# management-i2c.net
KiCad netlist of a schematic drawn in Altium Designer
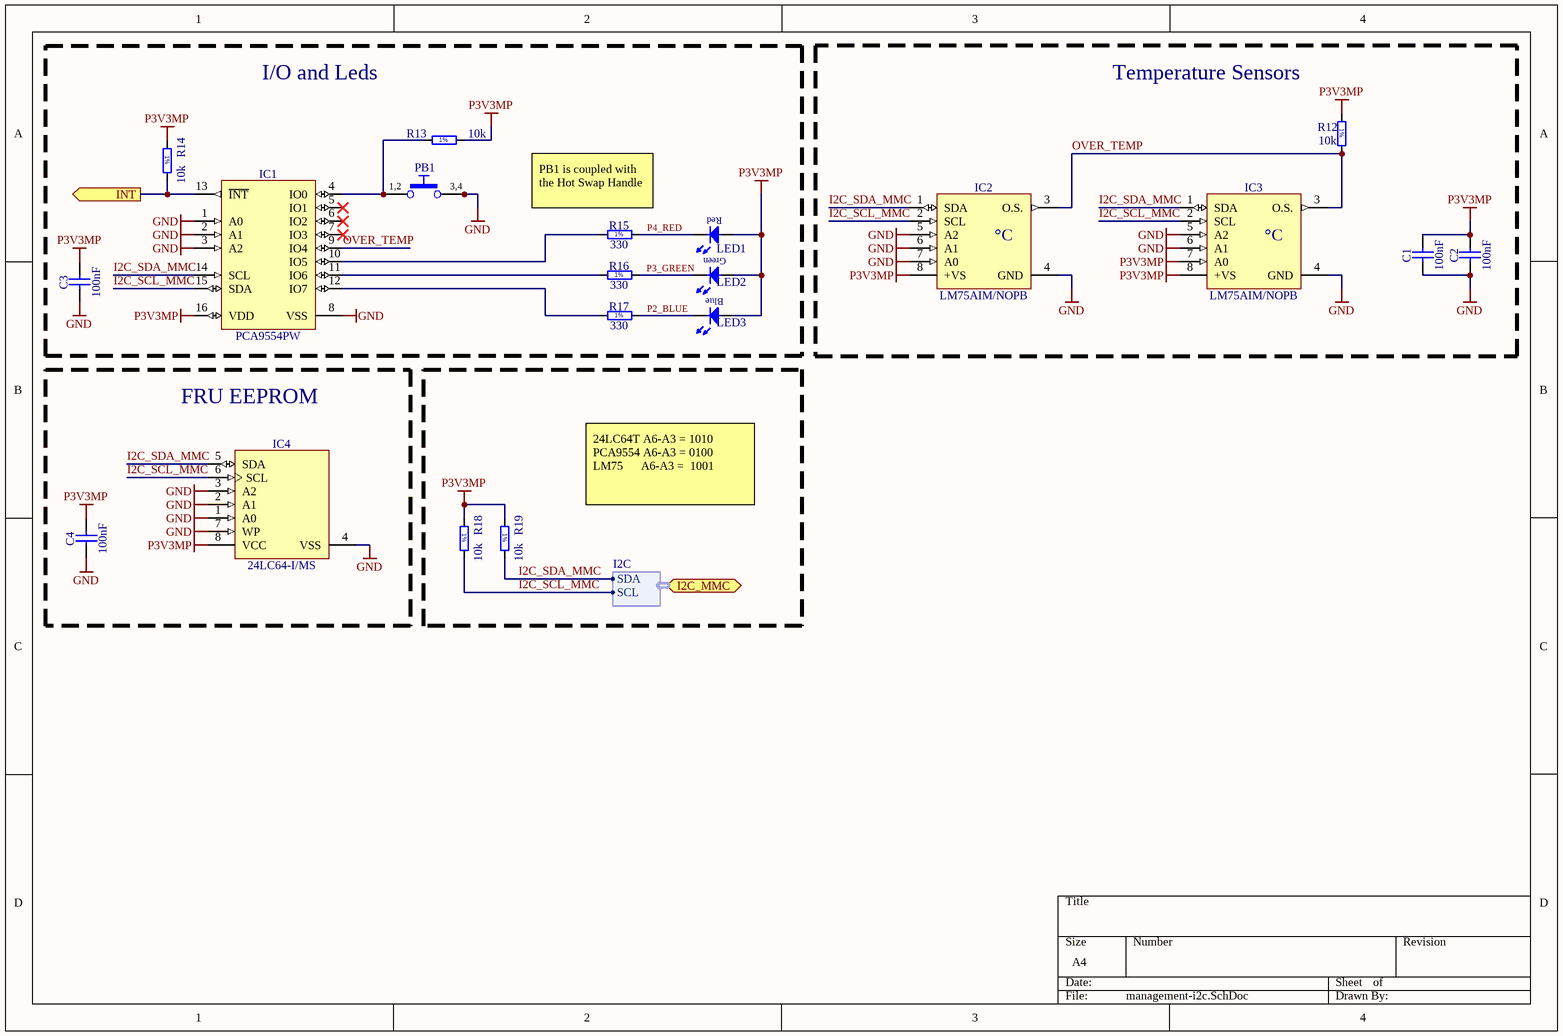
[diagram p0: management-i2c.SchDoc]

(export (version "E")
  (design (tool "Eeschema 10.0.6"))
  (components
    (comp (ref "C1")
      (value "100nF")
      (footprint "CAPC1005X55N")
      (description "Non-polarised capacitor")
      (fields
        (field (name "PART NUMBER") "CC0402_100NF_16V_10%_X7R")
        (field (name "VOLTAGE") "16V")
        (field (name "AUTHOR") "CERN DEM JLC")
      )
      (libsource (lib "Capacitors") (part "Capacitor - non polarized"))
    )
    (comp (ref "C2")
      (value "100nF")
      (footprint "CAPC1005X55N")
      (description "Non-polarised capacitor")
      (fields
        (field (name "PART NUMBER") "CC0402_100NF_16V_10%_X7R")
        (field (name "VOLTAGE") "16V")
        (field (name "AUTHOR") "CERN DEM JLC")
      )
      (libsource (lib "Capacitors") (part "Capacitor - non polarized"))
    )
    (comp (ref "C3")
      (value "100nF")
      (footprint "CAPC1005X55N")
      (description "Non-polarised capacitor")
      (fields
        (field (name "PART NUMBER") "CC0402_100NF_16V_10%_X7R")
        (field (name "VOLTAGE") "16V")
        (field (name "AUTHOR") "CERN DEM JLC")
      )
      (libsource (lib "Capacitors") (part "Capacitor - non polarized"))
    )
    (comp (ref "C4")
      (value "100nF")
      (footprint "CAPC1005X55N")
      (description "Non-polarised capacitor")
      (fields
        (field (name "PART NUMBER") "CC0402_100NF_16V_10%_X7R")
        (field (name "VOLTAGE") "16V")
        (field (name "AUTHOR") "CERN DEM JLC")
      )
      (libsource (lib "Capacitors") (part "Capacitor - non polarized"))
    )
    (comp (ref "IC1")
      (value "PCA9554PW")
      (footprint "SOP65P640X110-16N")
      (description "8-Bit I2C-Bus and SMBus I/O Port with Interrupt")
      (fields (field (name "MANUFACTURER") "NXP SEMICONDUCTORS") (field (name "AUTHOR") "CERN DEM JLC"))
      (libsource (lib "ICs And Semiconductors") (part "PCA9554PW"))
    )
    (comp (ref "IC2")
      (value "LM75AIM/NOPB")
      (footprint "SOIC127P600X175-8N")
      (description "Digital Temperature Sensor and Thermal Watchdog with Two-Wire Interface")
      (fields (field (name "MANUFACTURER") "TEXAS INSTRUMENTS") (field (name "AUTHOR") "CERN DEM JLC"))
      (libsource (lib "ICs And Semiconductors") (part "LM75"))
    )
    (comp (ref "IC3")
      (value "LM75AIM/NOPB")
      (footprint "SOIC127P600X175-8N")
      (description "Digital Temperature Sensor and Thermal Watchdog with Two-Wire Interface")
      (fields (field (name "MANUFACTURER") "TEXAS INSTRUMENTS") (field (name "AUTHOR") "CERN DEM JLC"))
      (libsource (lib "ICs And Semiconductors") (part "LM75"))
    )
    (comp (ref "IC4")
      (value "24LC64-I/MS")
      (footprint "SOP65P490X110-8N")
      (description "64K I2C Serial EEPROM")
      (fields (field (name "MANUFACTURER") "MICROCHIP TECHNOLOGY") (field (name "AUTHOR") "CERN DEM JLC"))
      (libsource (lib "ICs And Semiconductors") (part "24LC64-I/MS"))
    )
    (comp (ref "LED1")
      (value "Red")
      (footprint "LEDC1608X80N_RED")
      (description "LED Red 1C 2A")
      (fields
        (field (name "PART NUMBER") "LED_ROHM_SML-311UTT86K")
        (field (name "MANUFACTURER") "ROHM")
        (field (name "AUTHOR") "CERN DEM JLC")
      )
      (libsource (lib "ICs And Semiconductors") (part "LED Red 1C 2A"))
    )
    (comp (ref "LED2")
      (value "Green")
      (footprint "LED_AVAGO_HSME-C120")
      (description "LED Green 1C 2A")
      (fields
        (field (name "PART NUMBER") "LED_AVAGO_HSME-C120")
        (field (name "MANUFACTURER") "AVAGO TECHNOLOGIES")
        (field (name "AUTHOR") "CERN DEM JMW")
      )
      (libsource (lib "ICs And Semiconductors") (part "LED Green 1C 2A"))
    )
    (comp (ref "LED3")
      (value "Blue")
      (footprint "LED_AVAGO_HSMR-C120")
      (description "LED Blue 1C 2A")
      (fields
        (field (name "PART NUMBER") "LED_AVAGO_HSMR-C120")
        (field (name "MANUFACTURER") "AVAGO TECHNOLOGIES")
        (field (name "AUTHOR") "CERN DEM JLC")
      )
      (libsource (lib "ICs And Semiconductors") (part "LED Blue 1C 2A"))
    )
    (comp (ref "PB1")
      (value "Push Button")
      (footprint "SW_C&K_HDT0001")
      (description "Push-Button Switch SPDT")
      (fields
        (field (name "PART NUMBER") "SW_C&K_HDT0001")
        (field (name "MANUFACTURER") "C&K")
        (field (name "AUTHOR") "CERN DEM JLC")
      )
      (libsource (lib "Eletro-mechanical") (part "PB SPST 12NO-34NO"))
    )
    (comp (ref "R12")
      (value "10k")
      (footprint "RESC1005X40N")
      (description "Resistor - 1%")
      (fields
        (field (name "PART NUMBER") "R0402_10K_1%_0.0625W_100PPM")
        (field (name "POWER") "0.0625W")
        (field (name "AUTHOR") "CERN DEM JLC")
      )
      (libsource (lib "Resistors") (part "Resistor - 1%"))
    )
    (comp (ref "R13")
      (value "10k")
      (footprint "RESC1005X40N")
      (description "Resistor - 1%")
      (fields
        (field (name "PART NUMBER") "R0402_10K_1%_0.0625W_100PPM")
        (field (name "POWER") "0.0625W")
        (field (name "AUTHOR") "CERN DEM JLC")
      )
      (libsource (lib "Resistors") (part "Resistor - 1%"))
    )
    (comp (ref "R14")
      (value "10k")
      (footprint "RESC1005X40N")
      (description "Resistor - 1%")
      (fields
        (field (name "PART NUMBER") "R0402_10K_1%_0.0625W_100PPM")
        (field (name "POWER") "0.0625W")
        (field (name "AUTHOR") "CERN DEM JLC")
      )
      (libsource (lib "Resistors") (part "Resistor - 1%"))
    )
    (comp (ref "R15")
      (value "330")
      (footprint "RESC1608X55N")
      (description "Resistor - 1%")
      (fields
        (field (name "PART NUMBER") "R0603_330R_1%_0.1W_100PPM")
        (field (name "POWER") "0.1W")
        (field (name "AUTHOR") "CERN DEM JLC")
      )
      (libsource (lib "Resistors") (part "Resistor - 1%"))
    )
    (comp (ref "R16")
      (value "330")
      (footprint "RESC1608X55N")
      (description "Resistor - 1%")
      (fields
        (field (name "PART NUMBER") "R0603_330R_1%_0.1W_100PPM")
        (field (name "POWER") "0.1W")
        (field (name "AUTHOR") "CERN DEM JLC")
      )
      (libsource (lib "Resistors") (part "Resistor - 1%"))
    )
    (comp (ref "R17")
      (value "330")
      (footprint "RESC1608X55N")
      (description "Resistor - 1%")
      (fields
        (field (name "PART NUMBER") "R0603_330R_1%_0.1W_100PPM")
        (field (name "POWER") "0.1W")
        (field (name "AUTHOR") "CERN DEM JLC")
      )
      (libsource (lib "Resistors") (part "Resistor - 1%"))
    )
    (comp (ref "R18")
      (value "10k")
      (footprint "RESC1005X40N")
      (description "Resistor - 1%")
      (fields
        (field (name "PART NUMBER") "R0402_10K_1%_0.0625W_100PPM")
        (field (name "POWER") "0.0625W")
        (field (name "AUTHOR") "CERN DEM JLC")
      )
      (libsource (lib "Resistors") (part "Resistor - 1%"))
    )
    (comp (ref "R19")
      (value "10k")
      (footprint "RESC1005X40N")
      (description "Resistor - 1%")
      (fields
        (field (name "PART NUMBER") "R0402_10K_1%_0.0625W_100PPM")
        (field (name "POWER") "0.0625W")
        (field (name "AUTHOR") "CERN DEM JLC")
      )
      (libsource (lib "Resistors") (part "Resistor - 1%"))
    )
  )
  (nets
    (net (code "2") (name "/I2C_SCL_MMC") (class "Default")
      (node (ref "IC1") (pin "15") (pinfunction "SDA_15") (pintype "bidirectional"))
      (node (ref "IC2") (pin "2") (pinfunction "SCL_2") (pintype "input"))
      (node (ref "IC3") (pin "2") (pinfunction "SCL_2") (pintype "input"))
      (node (ref "IC4") (pin "6") (pinfunction "SCL_6") (pintype "input"))
      (node (ref "R18") (pin "2") (pinfunction "2_2") (pintype "passive"))
    )
    (net (code "3") (name "/I2C_SDA_MMC") (class "Default")
      (node (ref "IC1") (pin "14") (pinfunction "SCL_14") (pintype "input"))
      (node (ref "IC2") (pin "1") (pinfunction "SDA_1") (pintype "bidirectional"))
      (node (ref "IC3") (pin "1") (pinfunction "SDA_1") (pintype "bidirectional"))
      (node (ref "IC4") (pin "5") (pinfunction "SDA_5") (pintype "bidirectional"))
      (node (ref "R19") (pin "2") (pinfunction "2_2") (pintype "passive"))
    )
    (net (code "4") (name "/INT") (class "Default")
      (node (ref "IC1") (pin "13") (pinfunction "~{INT}_13") (pintype "output"))
      (node (ref "R14") (pin "2") (pinfunction "2_2") (pintype "passive"))
    )
    (net (code "5") (name "/OVER_TEMP") (class "Default")
      (node (ref "IC1") (pin "9") (pinfunction "IO4_9") (pintype "bidirectional"))
      (node (ref "IC2") (pin "3") (pinfunction "O.S._3") (pintype "output"))
      (node (ref "IC3") (pin "3") (pinfunction "O.S._3") (pintype "output"))
      (node (ref "R12") (pin "2") (pinfunction "2_2") (pintype "passive"))
    )
    (net (code "6") (name "/P2_BLUE") (class "Default")
      (node (ref "LED3") (pin "1") (pinfunction "C_1") (pintype "passive"))
      (node (ref "R17") (pin "2") (pinfunction "2_2") (pintype "passive"))
    )
    (net (code "7") (name "/P3_GREEN") (class "Default")
      (node (ref "LED2") (pin "1") (pinfunction "C_1") (pintype "passive"))
      (node (ref "R16") (pin "2") (pinfunction "2_2") (pintype "passive"))
    )
    (net (code "8") (name "/P4_RED") (class "Default")
      (node (ref "LED1") (pin "1") (pinfunction "C_1") (pintype "passive"))
      (node (ref "R15") (pin "2") (pinfunction "2_2") (pintype "passive"))
    )
    (net (code "10") (name "GND") (class "Default")
      (node (ref "C1") (pin "2") (pinfunction "2_2") (pintype "passive"))
      (node (ref "C2") (pin "2") (pinfunction "2_2") (pintype "passive"))
      (node (ref "C3") (pin "2") (pinfunction "2_2") (pintype "passive"))
      (node (ref "C4") (pin "2") (pinfunction "2_2") (pintype "passive"))
      (node (ref "IC1") (pin "1") (pinfunction "A0_1") (pintype "input"))
      (node (ref "IC1") (pin "2") (pinfunction "A1_2") (pintype "input"))
      (node (ref "IC1") (pin "3") (pinfunction "A2_3") (pintype "input"))
      (node (ref "IC1") (pin "8") (pinfunction "VSS_8") (pintype "power_in"))
      (node (ref "IC2") (pin "4") (pinfunction "GND_4") (pintype "power_in"))
      (node (ref "IC2") (pin "5") (pinfunction "A2_5") (pintype "input"))
      (node (ref "IC2") (pin "6") (pinfunction "A1_6") (pintype "input"))
      (node (ref "IC2") (pin "7") (pinfunction "A0_7") (pintype "input"))
      (node (ref "IC3") (pin "4") (pinfunction "GND_4") (pintype "power_in"))
      (node (ref "IC3") (pin "5") (pinfunction "A2_5") (pintype "input"))
      (node (ref "IC3") (pin "6") (pinfunction "A1_6") (pintype "input"))
      (node (ref "IC4") (pin "1") (pinfunction "A0_1") (pintype "input"))
      (node (ref "IC4") (pin "2") (pinfunction "A1_2") (pintype "input"))
      (node (ref "IC4") (pin "3") (pinfunction "A2_3") (pintype "input"))
      (node (ref "IC4") (pin "4") (pinfunction "VSS_4") (pintype "power_in"))
      (node (ref "IC4") (pin "7") (pinfunction "WP_7") (pintype "input"))
      (node (ref "PB1") (pin "3") (pinfunction "3_3") (pintype "passive"))
      (node (ref "PB1") (pin "4") (pinfunction "4_4") (pintype "passive"))
    )
    (net (code "11") (name "Net-(IC1-IO0)") (class "Default")
      (node (ref "IC1") (pin "4") (pinfunction "IO0_4") (pintype "bidirectional"))
      (node (ref "PB1") (pin "1") (pinfunction "1_1") (pintype "passive"))
      (node (ref "PB1") (pin "2") (pinfunction "2_2") (pintype "passive"))
      (node (ref "R13") (pin "1") (pinfunction "1_1") (pintype "passive"))
    )
    (net (code "12") (name "Net-(IC1-IO5)") (class "Default")
      (node (ref "IC1") (pin "10") (pinfunction "IO5_10") (pintype "bidirectional"))
      (node (ref "R15") (pin "1") (pinfunction "1_1") (pintype "passive"))
    )
    (net (code "13") (name "Net-(IC1-IO6)") (class "Default")
      (node (ref "IC1") (pin "11") (pinfunction "IO6_11") (pintype "bidirectional"))
      (node (ref "R16") (pin "1") (pinfunction "1_1") (pintype "passive"))
    )
    (net (code "14") (name "Net-(IC1-IO7)") (class "Default")
      (node (ref "IC1") (pin "12") (pinfunction "IO7_12") (pintype "bidirectional"))
      (node (ref "R17") (pin "1") (pinfunction "1_1") (pintype "passive"))
    )
    (net (code "15") (name "P3V3MP") (class "Default")
      (node (ref "C1") (pin "1") (pinfunction "1_1") (pintype "passive"))
      (node (ref "C2") (pin "1") (pinfunction "1_1") (pintype "passive"))
      (node (ref "C3") (pin "1") (pinfunction "1_1") (pintype "passive"))
      (node (ref "C4") (pin "1") (pinfunction "1_1") (pintype "passive"))
      (node (ref "IC1") (pin "16") (pinfunction "VDD_16") (pintype "bidirectional"))
      (node (ref "IC2") (pin "8") (pinfunction "+VS_8") (pintype "power_in"))
      (node (ref "IC3") (pin "7") (pinfunction "A0_7") (pintype "input"))
      (node (ref "IC3") (pin "8") (pinfunction "+VS_8") (pintype "power_in"))
      (node (ref "IC4") (pin "8") (pinfunction "VCC_8") (pintype "power_in"))
      (node (ref "LED1") (pin "2") (pinfunction "A_2") (pintype "passive"))
      (node (ref "LED2") (pin "2") (pinfunction "A_2") (pintype "passive"))
      (node (ref "LED3") (pin "2") (pinfunction "A_2") (pintype "passive"))
      (node (ref "R12") (pin "1") (pinfunction "1_1") (pintype "passive"))
      (node (ref "R13") (pin "2") (pinfunction "2_2") (pintype "passive"))
      (node (ref "R14") (pin "1") (pinfunction "1_1") (pintype "passive"))
      (node (ref "R18") (pin "1") (pinfunction "1_1") (pintype "passive"))
      (node (ref "R19") (pin "1") (pinfunction "1_1") (pintype "passive"))
    )
    (net (code "16") (name "unconnected-(IC1-IO1-Pad5)") (class "Default")
      (node (ref "IC1") (pin "5") (pinfunction "IO1_5") (pintype "bidirectional+no_connect"))
    )
    (net (code "17") (name "unconnected-(IC1-IO2-Pad6)") (class "Default")
      (node (ref "IC1") (pin "6") (pinfunction "IO2_6") (pintype "bidirectional+no_connect"))
    )
    (net (code "18") (name "unconnected-(IC1-IO3-Pad7)") (class "Default")
      (node (ref "IC1") (pin "7") (pinfunction "IO3_7") (pintype "bidirectional+no_connect"))
    )
  )
)
